# circuit.net
KiCad netlist of a schematic drawn in EAGLE
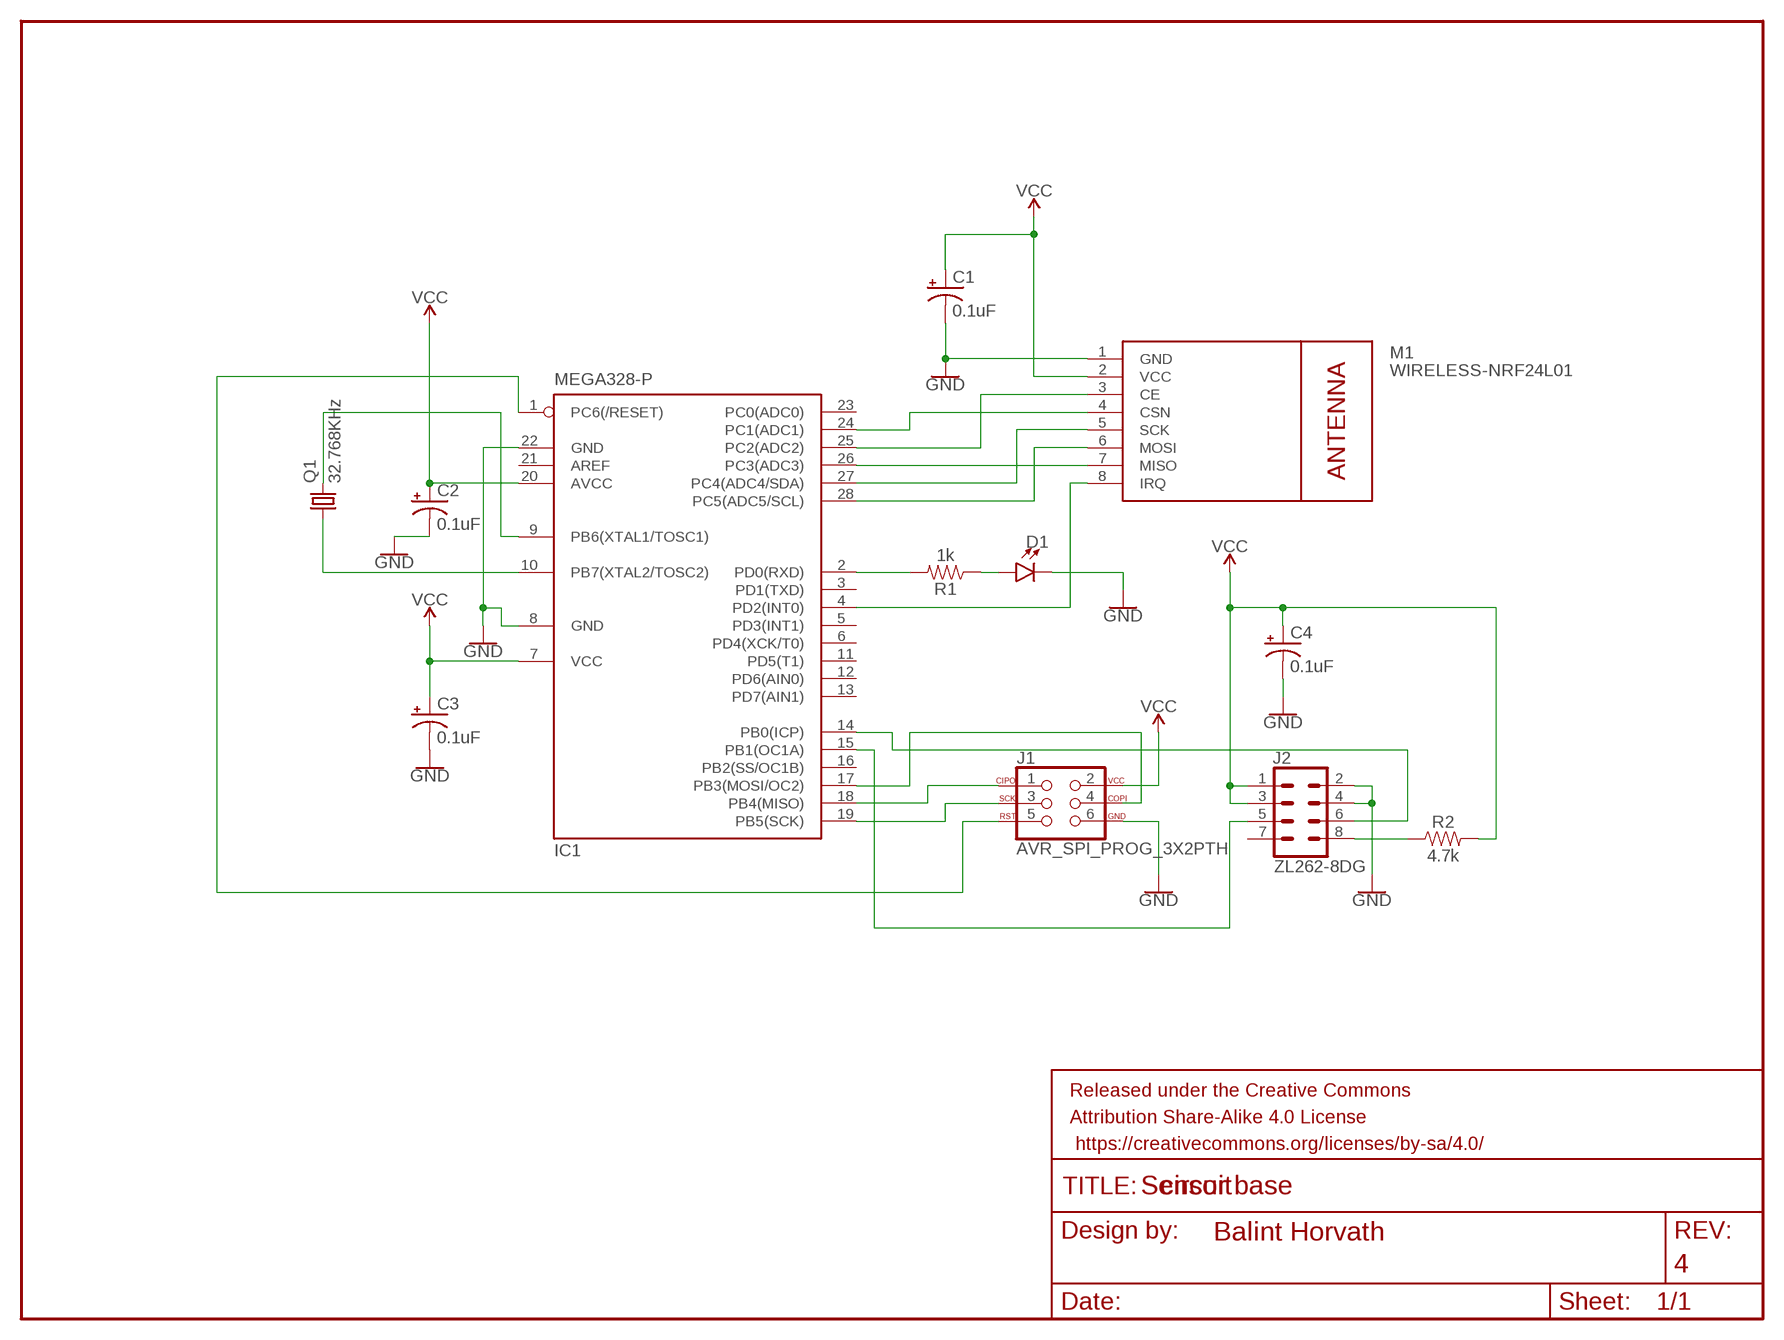
[diagram p0: schematic, sheet 1]

(export (version "E")
  (design (tool "Eeschema 10.0.6"))
  (components
    (comp (ref "C1")
      (value "0.1uF")
      (footprint "eagle-import:CPOL-RADIAL-2.5MM-5MM")
      (libsource (lib "eagle-import") (part "0.1UF-POLAR-RADIAL-2.5MM-25V-20%"))
    )
    (comp (ref "C2")
      (value "0.1uF")
      (footprint "eagle-import:CPOL-RADIAL-2.5MM-5MM")
      (libsource (lib "eagle-import") (part "0.1UF-POLAR-RADIAL-2.5MM-25V-20%"))
    )
    (comp (ref "C3")
      (value "0.1uF")
      (footprint "eagle-import:CPOL-RADIAL-2.5MM-5MM")
      (libsource (lib "eagle-import") (part "0.1UF-POLAR-RADIAL-2.5MM-25V-20%"))
    )
    (comp (ref "C4")
      (value "0.1uF")
      (footprint "eagle-import:CPOL-RADIAL-2.5MM-5MM")
      (libsource (lib "eagle-import") (part "0.1UF-POLAR-RADIAL-2.5MM-25V-20%"))
    )
    (comp (ref "D1")
      (value "LED5MM")
      (footprint "eagle-import:LED_5MM")
      (libsource (lib "eagle-import") (part "LED5MM"))
    )
    (comp (ref "FRAME1")
      (value "FRAME-LETTER")
      (footprint "eagle-import:CREATIVE_COMMONS")
      (fields (field (name "DESIGNER") "Balint Horvath") (field (name "REV") "4"))
      (libsource (lib "eagle-import") (part "FRAME-LETTER"))
    )
    (comp (ref "IC1")
      (value "MEGA328-P")
      (footprint "eagle-import:DIL28-3")
      (libsource (lib "eagle-import") (part "MEGA8-P"))
    )
    (comp (ref "J1")
      (value "AVR_SPI_PROG_3X2PTH")
      (footprint "eagle-import:2X3")
      (libsource (lib "eagle-import") (part "AVR_SPI_PROG_3X2PTH"))
    )
    (comp (ref "J2")
      (value "ZL262-8DG")
      (footprint "eagle-import:2X4")
      (libsource (lib "eagle-import") (part "CONN_04X2"))
    )
    (comp (ref "M1")
      (value "WIRELESS-NRF24L01")
      (footprint "eagle-import:WIRELESS-NRF24L01")
      (libsource (lib "eagle-import") (part "WIRELESS-NRF24L01"))
    )
    (comp (ref "Q1")
      (value "32.768KHz")
      (footprint "eagle-import:TC26V")
      (libsource (lib "eagle-import") (part "CRYSTALTC26V"))
    )
    (comp (ref "R1")
      (value "1k")
      (footprint "eagle-import:AXIAL-0.3")
      (libsource (lib "eagle-import") (part "SparkFun-Resistors_1KOHM-HORIZ-1/4W-1%"))
    )
    (comp (ref "R2")
      (value "4.7k")
      (footprint "eagle-import:AXIAL-0.3")
      (libsource (lib "eagle-import") (part "1KOHM-HORIZ-1/4W-1%"))
    )
  )
  (nets
    (net (code "1") (name "GND") (class "Default")
      (node (ref "C1") (pin "2") (pinfunction "-_2") (pintype "passive"))
      (node (ref "C2") (pin "2") (pinfunction "-_2") (pintype "passive"))
      (node (ref "C3") (pin "2") (pinfunction "-_2") (pintype "passive"))
      (node (ref "C4") (pin "2") (pinfunction "-_2") (pintype "passive"))
      (node (ref "D1") (pin "K") (pinfunction "C_K") (pintype "passive"))
      (node (ref "IC1") (pin "22") (pinfunction "GND_22") (pintype "power_in"))
      (node (ref "IC1") (pin "8") (pinfunction "GND_8") (pintype "power_in"))
      (node (ref "J1") (pin "6") (pinfunction "6_6") (pintype "passive"))
      (node (ref "J2") (pin "2") (pinfunction "2_2") (pintype "passive"))
      (node (ref "J2") (pin "4") (pinfunction "4_4") (pintype "passive"))
      (node (ref "M1") (pin "1") (pinfunction "GND_1") (pintype "power_in"))
    )
    (net (code "2") (name "Net-(IC1-PB0(ICP))") (class "Default")
      (node (ref "IC1") (pin "14") (pinfunction "PB0(ICP)_14") (pintype "bidirectional"))
      (node (ref "J2") (pin "6") (pinfunction "6_6") (pintype "passive"))
    )
    (net (code "3") (name "Net-(IC1-PB1(OC1A))") (class "Default")
      (node (ref "IC1") (pin "15") (pinfunction "PB1(OC1A)_15") (pintype "bidirectional"))
      (node (ref "J2") (pin "5") (pinfunction "5_5") (pintype "passive"))
    )
    (net (code "4") (name "Net-(IC1-PB3(MOSI{slash}OC2))") (class "Default")
      (node (ref "IC1") (pin "17") (pinfunction "PB3(MOSI/OC2)_17") (pintype "bidirectional"))
      (node (ref "J1") (pin "4") (pinfunction "4_4") (pintype "passive"))
    )
    (net (code "5") (name "Net-(IC1-PB4(MISO))") (class "Default")
      (node (ref "IC1") (pin "18") (pinfunction "PB4(MISO)_18") (pintype "bidirectional"))
      (node (ref "J1") (pin "1") (pinfunction "1_1") (pintype "passive"))
    )
    (net (code "6") (name "Net-(IC1-PB5(SCK))") (class "Default")
      (node (ref "IC1") (pin "19") (pinfunction "PB5(SCK)_19") (pintype "bidirectional"))
      (node (ref "J1") (pin "3") (pinfunction "3_3") (pintype "passive"))
    )
    (net (code "7") (name "Net-(IC1-PB6(XTAL1{slash}TOSC1))") (class "Default")
      (node (ref "IC1") (pin "9") (pinfunction "PB6(XTAL1/TOSC1)_9") (pintype "bidirectional"))
      (node (ref "Q1") (pin "2") (pinfunction "2_2") (pintype "passive"))
    )
    (net (code "8") (name "Net-(IC1-PB7(XTAL2{slash}TOSC2))") (class "Default")
      (node (ref "IC1") (pin "10") (pinfunction "PB7(XTAL2/TOSC2)_10") (pintype "bidirectional"))
      (node (ref "Q1") (pin "1") (pinfunction "1_1") (pintype "passive"))
    )
    (net (code "9") (name "Net-(IC1-PC1(ADC1))") (class "Default")
      (node (ref "IC1") (pin "24") (pinfunction "PC1(ADC1)_24") (pintype "bidirectional"))
      (node (ref "M1") (pin "4") (pinfunction "CSN_4") (pintype "bidirectional"))
    )
    (net (code "10") (name "Net-(IC1-PC2(ADC2))") (class "Default")
      (node (ref "IC1") (pin "25") (pinfunction "PC2(ADC2)_25") (pintype "bidirectional"))
      (node (ref "M1") (pin "3") (pinfunction "CE_3") (pintype "bidirectional"))
    )
    (net (code "11") (name "Net-(IC1-PC3(ADC3))") (class "Default")
      (node (ref "IC1") (pin "26") (pinfunction "PC3(ADC3)_26") (pintype "bidirectional"))
      (node (ref "M1") (pin "7") (pinfunction "MISO_7") (pintype "bidirectional"))
    )
    (net (code "12") (name "Net-(IC1-PC4(ADC4{slash}SDA))") (class "Default")
      (node (ref "IC1") (pin "27") (pinfunction "PC4(ADC4/SDA)_27") (pintype "bidirectional"))
      (node (ref "M1") (pin "5") (pinfunction "SCK_5") (pintype "bidirectional"))
    )
    (net (code "13") (name "Net-(IC1-PC5(ADC5{slash}SCL))") (class "Default")
      (node (ref "IC1") (pin "28") (pinfunction "PC5(ADC5/SCL)_28") (pintype "bidirectional"))
      (node (ref "M1") (pin "6") (pinfunction "MOSI_6") (pintype "bidirectional"))
    )
    (net (code "14") (name "Net-(IC1-PC6({slash}RESET))") (class "Default")
      (node (ref "IC1") (pin "1") (pinfunction "PC6(/RESET)_1") (pintype "bidirectional"))
      (node (ref "J1") (pin "5") (pinfunction "5_5") (pintype "passive"))
    )
    (net (code "15") (name "Net-(IC1-PD0(RXD))") (class "Default")
      (node (ref "IC1") (pin "2") (pinfunction "PD0(RXD)_2") (pintype "bidirectional"))
      (node (ref "R1") (pin "P$2") (pinfunction "2_P$2") (pintype "passive"))
    )
    (net (code "16") (name "Net-(IC1-PD2(INT0))") (class "Default")
      (node (ref "IC1") (pin "4") (pinfunction "PD2(INT0)_4") (pintype "bidirectional"))
      (node (ref "M1") (pin "8") (pinfunction "IRQ_8") (pintype "bidirectional"))
    )
    (net (code "17") (name "Net-(R1-1)") (class "Default")
      (node (ref "D1") (pin "A") (pinfunction "A_A") (pintype "passive"))
      (node (ref "R1") (pin "P$1") (pinfunction "1_P$1") (pintype "passive"))
    )
    (net (code "18") (name "Net-(R2-1)") (class "Default")
      (node (ref "J2") (pin "8") (pinfunction "8_8") (pintype "passive"))
      (node (ref "R2") (pin "P$1") (pinfunction "1_P$1") (pintype "passive"))
    )
    (net (code "19") (name "VCC") (class "Default")
      (node (ref "C1") (pin "1") (pinfunction "+_1") (pintype "passive"))
      (node (ref "C2") (pin "1") (pinfunction "+_1") (pintype "passive"))
      (node (ref "C3") (pin "1") (pinfunction "+_1") (pintype "passive"))
      (node (ref "C4") (pin "1") (pinfunction "+_1") (pintype "passive"))
      (node (ref "IC1") (pin "20") (pinfunction "AVCC_20") (pintype "power_in"))
      (node (ref "IC1") (pin "7") (pinfunction "VCC_7") (pintype "power_in"))
      (node (ref "J1") (pin "2") (pinfunction "2_2") (pintype "passive"))
      (node (ref "J2") (pin "1") (pinfunction "1_1") (pintype "passive"))
      (node (ref "J2") (pin "3") (pinfunction "3_3") (pintype "passive"))
      (node (ref "M1") (pin "2") (pinfunction "VCC_2") (pintype "power_in"))
      (node (ref "R2") (pin "P$2") (pinfunction "2_P$2") (pintype "passive"))
    )
    (net (code "20") (name "unconnected-(IC1-AREF-Pad21)") (class "Default")
      (node (ref "IC1") (pin "21") (pinfunction "AREF_21") (pintype "passive"))
    )
    (net (code "21") (name "unconnected-(IC1-PB2(SS{slash}OC1B)-Pad16)") (class "Default")
      (node (ref "IC1") (pin "16") (pinfunction "PB2(SS/OC1B)_16") (pintype "bidirectional"))
    )
    (net (code "22") (name "unconnected-(IC1-PC0(ADC0)-Pad23)") (class "Default")
      (node (ref "IC1") (pin "23") (pinfunction "PC0(ADC0)_23") (pintype "bidirectional"))
    )
    (net (code "23") (name "unconnected-(IC1-PD1(TXD)-Pad3)") (class "Default")
      (node (ref "IC1") (pin "3") (pinfunction "PD1(TXD)_3") (pintype "bidirectional"))
    )
    (net (code "24") (name "unconnected-(IC1-PD3(INT1)-Pad5)") (class "Default")
      (node (ref "IC1") (pin "5") (pinfunction "PD3(INT1)_5") (pintype "bidirectional"))
    )
    (net (code "25") (name "unconnected-(IC1-PD4(XCK{slash}T0)-Pad6)") (class "Default")
      (node (ref "IC1") (pin "6") (pinfunction "PD4(XCK/T0)_6") (pintype "bidirectional"))
    )
    (net (code "26") (name "unconnected-(IC1-PD5(T1)-Pad11)") (class "Default")
      (node (ref "IC1") (pin "11") (pinfunction "PD5(T1)_11") (pintype "bidirectional"))
    )
    (net (code "27") (name "unconnected-(IC1-PD6(AIN0)-Pad12)") (class "Default")
      (node (ref "IC1") (pin "12") (pinfunction "PD6(AIN0)_12") (pintype "bidirectional"))
    )
    (net (code "28") (name "unconnected-(IC1-PD7(AIN1)-Pad13)") (class "Default")
      (node (ref "IC1") (pin "13") (pinfunction "PD7(AIN1)_13") (pintype "bidirectional"))
    )
    (net (code "29") (name "unconnected-(J2-Pad7)") (class "Default")
      (node (ref "J2") (pin "7") (pinfunction "7_7") (pintype "passive"))
    )
  )
)
